# Button.net
KiCad netlist of a schematic drawn in EAGLE
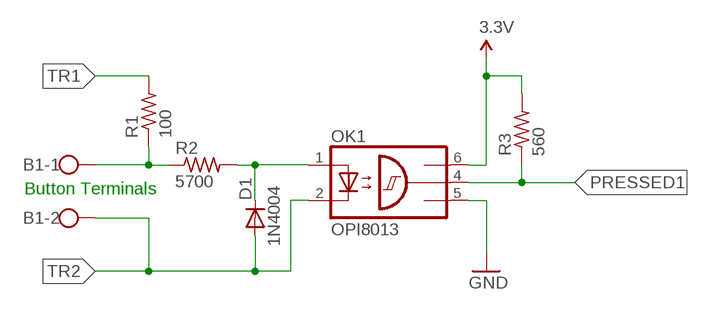
[diagram p0: schematic, sheet 1]

(export (version "E")
  (design (tool "Eeschema 10.0.6"))
  (components
    (comp (ref "B1")
      (value "W237-102")
      (footprint "eagle-import:W237-102")
      (fields (field (name "MPN") "237-102"))
      (libsource (lib "eagle-import") (part "W237-102"))
    )
    (comp (ref "D1")
      (value "1N4004")
      (footprint "eagle-import:DO41-10")
      (libsource (lib "eagle-import") (part "1N4004"))
    )
    (comp (ref "OK1")
      (value "OPI8013")
      (footprint "eagle-import:DIL06")
      (libsource (lib "eagle-import") (part "OPI8013"))
    )
    (comp (ref "R1")
      (value "100")
      (footprint "eagle-import:P0817_22")
      (libsource (lib "eagle-import") (part "R-US_0817/22"))
    )
    (comp (ref "R2")
      (value "5700")
      (footprint "eagle-import:0207_12")
      (libsource (lib "eagle-import") (part "R-US_0207/12"))
    )
    (comp (ref "R3")
      (value "560")
      (footprint "eagle-import:0207_7")
      (libsource (lib "eagle-import") (part "R-US_0207/7"))
    )
  )
  (nets
    (net (code "1") (name "3.3V") (class "Default")
      (node (ref "OK1") (pin "6") (pinfunction "VCC_6") (pintype "passive"))
      (node (ref "R3") (pin "2") (pinfunction "2_2") (pintype "passive"))
    )
    (net (code "2") (name "GND") (class "Default")
      (node (ref "OK1") (pin "5") (pinfunction "GND_5") (pintype "passive"))
    )
    (net (code "3") (name "Net-(B1A-KL)") (class "Default")
      (node (ref "B1") (pin "1") (pinfunction "KL_1") (pintype "passive"))
      (node (ref "R1") (pin "1") (pinfunction "1_1") (pintype "passive"))
      (node (ref "R2") (pin "1") (pinfunction "1_1") (pintype "passive"))
    )
    (net (code "4") (name "Net-(OK1-A)") (class "Default")
      (node (ref "D1") (pin "C") (pinfunction "C_C") (pintype "passive"))
      (node (ref "OK1") (pin "1") (pinfunction "A_1") (pintype "passive"))
      (node (ref "R2") (pin "2") (pinfunction "2_2") (pintype "passive"))
    )
    (net (code "5") (name "PRESSED1") (class "Default")
      (node (ref "OK1") (pin "4") (pinfunction "OUT_4") (pintype "passive"))
      (node (ref "R3") (pin "1") (pinfunction "1_1") (pintype "passive"))
    )
    (net (code "6") (name "TR1") (class "Default")
      (node (ref "R1") (pin "2") (pinfunction "2_2") (pintype "passive"))
    )
    (net (code "7") (name "TR2") (class "Default")
      (node (ref "B1") (pin "2") (pinfunction "KL_2") (pintype "passive"))
      (node (ref "D1") (pin "A") (pinfunction "A_A") (pintype "passive"))
      (node (ref "OK1") (pin "2") (pinfunction "C_2") (pintype "passive"))
    )
  )
)
